# 1_ESP32Main.net
KiCad netlist of a schematic drawn in Altium Designer
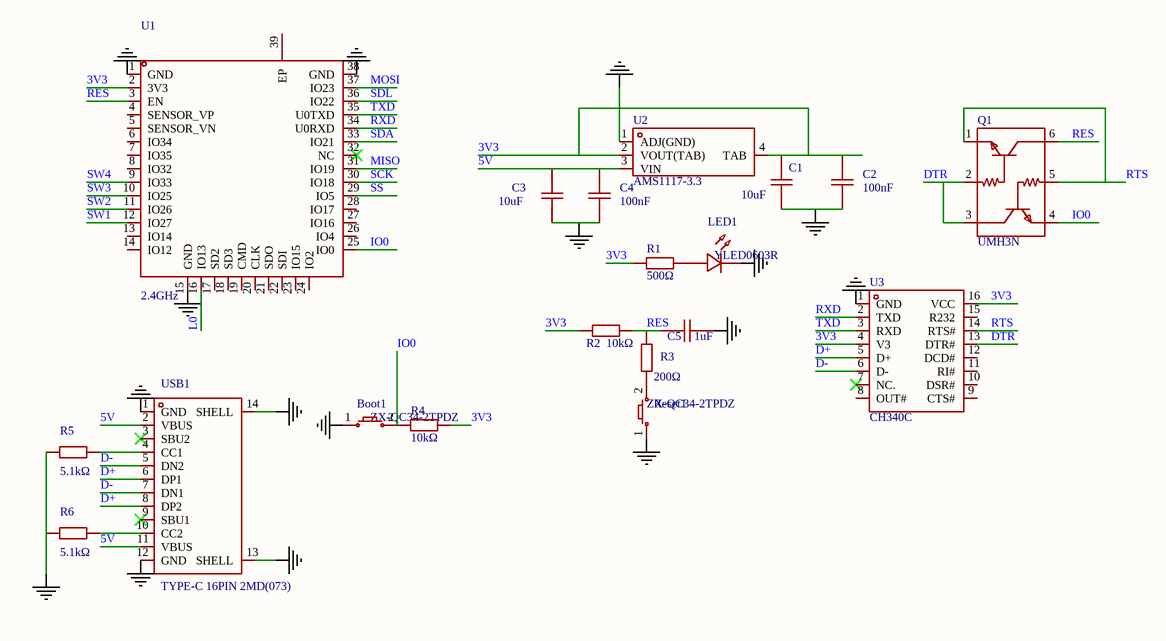
[diagram p0: 1_ESP32Main.schdoc]

(export (version "E")
  (design (tool "Eeschema 10.0.6"))
  (components
    (comp (ref "Boot1")
      (value "ZX-QC34-2TPDZ")
      (fields (field (name "MANUFACTURER") "Megastar(兆星)"))
      (libsource (lib "altium-import") (part "root_0_ZX-QC34-2TPDZ_"))
    )
    (comp (ref "C1")
      (value "10uF")
      (description "容值:10uF;精度:±20%;额定电压:25V;材质(温度系数):X5R;")
      (fields
        (field (name "MANUFACTURER") "SAMSUNG(三星)")
        (field (name "MANUFACTURER PART") "CL10A106MA8NRNC")
      )
      (libsource (lib "altium-import") (part "root_3_CL10A106MA8NRNC_"))
    )
    (comp (ref "C2")
      (value "100nF")
      (description "容值:100nF;精度:±10%;额定电压:50V;材质(温度系数):X7R;")
      (fields
        (field (name "MANUFACTURER") "HRE(芯声)")
        (field (name "MANUFACTURER PART") "CGA0603X7R104K500JT")
      )
      (libsource (lib "altium-import") (part "root_1_CGA0603X7R104K500JT_"))
    )
    (comp (ref "C3")
      (value "10uF")
      (description "容值:10uF;精度:±20%;额定电压:25V;材质(温度系数):X5R;")
      (fields
        (field (name "MANUFACTURER") "SAMSUNG(三星)")
        (field (name "MANUFACTURER PART") "CL10A106MA8NRNC")
      )
      (libsource (lib "altium-import") (part "root_1_CL10A106MA8NRNC_"))
    )
    (comp (ref "C4")
      (value "100nF")
      (description "容值:100nF;精度:±10%;额定电压:50V;材质(温度系数):X7R;")
      (fields
        (field (name "MANUFACTURER") "HRE(芯声)")
        (field (name "MANUFACTURER PART") "CGA0603X7R104K500JT")
      )
      (libsource (lib "altium-import") (part "root_1_CGA0603X7R104K500JT_"))
    )
    (comp (ref "C5")
      (value "1uF")
      (description "容值:1uF;精度:±10%;额定电压:50V;材质(温度系数):X5R;")
      (fields
        (field (name "MANUFACTURER") "SAMSUNG(三星)")
        (field (name "MANUFACTURER PART") "CL10A105KB8NNNC")
      )
      (libsource (lib "altium-import") (part "root_0_CL10A105KB8NNNC_"))
    )
    (comp (ref "LED1")
      (value "YLED0603R")
      (fields (field (name "MANUFACTURER") "YONGYUTAI(永裕泰)"))
      (libsource (lib "altium-import") (part "root_0_YLED0603R_"))
    )
    (comp (ref "Q1")
      (value "UMH3N")
      (description "晶体管类型:2个NPN-预偏置;集射极击穿电压(Vceo):50V;集电极电流(Ic):100mA;功率(Pd):150mW;")
      (fields (field (name "MANUFACTURER") "CJ(江苏长电/长晶)"))
      (libsource (lib "altium-import") (part "root_3_UMH3N_"))
    )
    (comp (ref "R1")
      (value "500Ω")
      (description "电阻类型:薄膜电阻;阻值:500Ω;精度:±0.1%;功率:100mW;温度系数:±15ppm/℃;")
      (fields (field (name "MANUFACTURER") "YAGEO(国巨)") (field (name "MANUFACTURER PART") "RT0603BRC07500RL"))
      (libsource (lib "altium-import") (part "root_0_RT0603BRC07500RL_"))
    )
    (comp (ref "R2")
      (value "10kΩ")
      (description "电阻类型:厚膜电阻;阻值:10kΩ;精度:±5%;功率:100mW;最大工作电压:75V;温度系数:±100ppm/℃;")
      (fields (field (name "MANUFACTURER") "FOJAN(富捷)") (field (name "MANUFACTURER PART") "FRC0603J103TS"))
      (libsource (lib "altium-import") (part "root_0_FRC0603J103TS_"))
    )
    (comp (ref "R3")
      (value "200Ω")
      (description "电阻类型:厚膜电阻;阻值:200Ω;精度:±1%;功率:100mW;最大工作电压:75V;温度系数:±100ppm/℃;")
      (fields
        (field (name "MANUFACTURER") "UNI-ROYAL(厚声)")
        (field (name "MANUFACTURER PART") "0603WAF2000T5E")
      )
      (libsource (lib "altium-import") (part "root_1_0603WAF2000T5E_"))
    )
    (comp (ref "R4")
      (value "10kΩ")
      (description "电阻类型:厚膜电阻;阻值:10kΩ;精度:±5%;功率:100mW;最大工作电压:75V;温度系数:±100ppm/℃;")
      (fields (field (name "MANUFACTURER") "FOJAN(富捷)") (field (name "MANUFACTURER PART") "FRC0603J103TS"))
      (libsource (lib "altium-import") (part "root_0_FRC0603J103TS_"))
    )
    (comp (ref "R5")
      (value "5.1kΩ")
      (description "电阻类型:厚膜电阻;阻值:5.1kΩ;精度:±1%;功率:100mW;最大工作电压:75V;温度系数:±100ppm/℃;")
      (fields
        (field (name "MANUFACTURER") "UNI-ROYAL(厚声)")
        (field (name "MANUFACTURER PART") "0603WAF5101T5E")
      )
      (libsource (lib "altium-import") (part "root_0_0603WAF5101T5E_"))
    )
    (comp (ref "R6")
      (value "5.1kΩ")
      (description "电阻类型:厚膜电阻;阻值:5.1kΩ;精度:±1%;功率:100mW;最大工作电压:75V;温度系数:±100ppm/℃;")
      (fields
        (field (name "MANUFACTURER") "UNI-ROYAL(厚声)")
        (field (name "MANUFACTURER PART") "0603WAF5101T5E")
      )
      (libsource (lib "altium-import") (part "root_0_0603WAF5101T5E_"))
    )
    (comp (ref "Reset1")
      (value "ZX-QC34-2TPDZ")
      (fields (field (name "MANUFACTURER") "Megastar(兆星)"))
      (libsource (lib "altium-import") (part "root_1_ZX-QC34-2TPDZ_"))
    )
    (comp (ref "U1")
      (value "2.4GHz")
      (description "核心处理器:ESP32芯片;频率:2.4GHz;天线形式:IPEX接口;发射功率:17dBm;接收灵敏度:-90dBm;")
      (fields (field (name "MANUFACTURER") "Ai-Thinker(安信可)") (field (name "MANUFACTURER PART") "ESP32-S"))
      (libsource (lib "altium-import") (part "root_0_ESP32-S_"))
    )
    (comp (ref "U2")
      (value "AMS1117-3.3")
      (description "输出类型:固定;最大输入电压:12V;输出电压:3.3V;最大输出电流:1A;电源纹波抑制比(PSRR):60dB@(120Hz);输出极性:正极;")
      (fields (field (name "MANUFACTURER") "UMW(友台半导体)"))
      (libsource (lib "altium-import") (part "root_0_AMS1117-3.3_C347222_"))
    )
    (comp (ref "U3")
      (value "CH340C")
      (description "应用功能:收发器;接口协议:USB 2.0;数据速率:2Mbps;")
      (fields (field (name "MANUFACTURER") "WCH(南京沁恒)"))
      (libsource (lib "altium-import") (part "root_0_CH340C_"))
    )
    (comp (ref "USB1")
      (value "TYPE-C 16PIN 2MD(073)")
      (description "连接器类型:Type-C;标准:USB 3.1;公母:母;安装方式:卧贴;触点数量:16P;端口数量:1;额定电流 - 电源:5A;工作温度范围:-25℃~+85℃;")
      (fields (field (name "MANUFACTURER") "SHOU HAN(首韩)"))
      (libsource (lib "altium-import") (part "root_0_TYPE-C 16PIN 2MD(073)_"))
    )
  )
  (nets
    (net (code "1") (name "/3V3") (class "Default")
      (node (ref "C1") (pin "1") (pinfunction "1_1") (pintype "passive"))
      (node (ref "C2") (pin "2") (pinfunction "2_2") (pintype "passive"))
      (node (ref "R1") (pin "1") (pinfunction "1_1") (pintype "passive"))
      (node (ref "R2") (pin "1") (pinfunction "1_1") (pintype "passive"))
      (node (ref "R4") (pin "2") (pinfunction "2_2") (pintype "passive"))
      (node (ref "U1") (pin "2") (pinfunction "3V3_2") (pintype "passive"))
      (node (ref "U2") (pin "2") (pinfunction "VOUT(TAB)_2") (pintype "passive"))
      (node (ref "U2") (pin "4") (pinfunction "TAB_4") (pintype "passive"))
      (node (ref "U3") (pin "16") (pinfunction "VCC_16") (pintype "passive"))
      (node (ref "U3") (pin "4") (pinfunction "V3_4") (pintype "passive"))
    )
    (net (code "2") (name "/5V") (class "Default")
      (node (ref "C3") (pin "2") (pinfunction "2_2") (pintype "passive"))
      (node (ref "C4") (pin "2") (pinfunction "2_2") (pintype "passive"))
      (node (ref "U2") (pin "3") (pinfunction "VIN_3") (pintype "passive"))
      (node (ref "USB1") (pin "11") (pinfunction "VBUS_11") (pintype "passive"))
      (node (ref "USB1") (pin "2") (pinfunction "VBUS_2") (pintype "passive"))
    )
    (net (code "3") (name "/D+") (class "Default")
      (node (ref "U3") (pin "5") (pinfunction "D+_5") (pintype "passive"))
      (node (ref "USB1") (pin "6") (pinfunction "DP1_6") (pintype "passive"))
      (node (ref "USB1") (pin "8") (pinfunction "DP2_8") (pintype "passive"))
    )
    (net (code "4") (name "/D-") (class "Default")
      (node (ref "U3") (pin "6") (pinfunction "D-_6") (pintype "passive"))
      (node (ref "USB1") (pin "5") (pinfunction "DN2_5") (pintype "passive"))
      (node (ref "USB1") (pin "7") (pinfunction "DN1_7") (pintype "passive"))
    )
    (net (code "5") (name "/DTR") (class "Default")
      (node (ref "Q1") (pin "2") (pinfunction "B_2") (pintype "passive"))
      (node (ref "Q1") (pin "3") (pinfunction "C_3") (pintype "passive"))
      (node (ref "U3") (pin "13") (pinfunction "DTR#_13") (pintype "passive"))
    )
    (net (code "6") (name "/IO0") (class "Default")
      (node (ref "Boot1") (pin "2") (pinfunction "2_2") (pintype "passive"))
      (node (ref "Q1") (pin "4") (pinfunction "E_4") (pintype "passive"))
      (node (ref "R4") (pin "1") (pinfunction "1_1") (pintype "passive"))
      (node (ref "U1") (pin "25") (pinfunction "IO0_25") (pintype "passive"))
    )
    (net (code "7") (name "/L0") (class "Default")
      (node (ref "U1") (pin "16") (pinfunction "IO13_16") (pintype "passive"))
    )
    (net (code "8") (name "/MISO") (class "Default")
      (node (ref "U1") (pin "31") (pinfunction "IO19_31") (pintype "passive"))
    )
    (net (code "9") (name "/MOSI") (class "Default")
      (node (ref "U1") (pin "37") (pinfunction "IO23_37") (pintype "passive"))
    )
    (net (code "10") (name "/RES") (class "Default")
      (node (ref "C5") (pin "1") (pinfunction "1_1") (pintype "passive"))
      (node (ref "Q1") (pin "6") (pinfunction "C_6") (pintype "passive"))
      (node (ref "R2") (pin "2") (pinfunction "2_2") (pintype "passive"))
      (node (ref "R3") (pin "2") (pinfunction "2_2") (pintype "passive"))
      (node (ref "U1") (pin "3") (pinfunction "EN_3") (pintype "passive"))
    )
    (net (code "11") (name "/RTS") (class "Default")
      (node (ref "Q1") (pin "1") (pinfunction "E_1") (pintype "passive"))
      (node (ref "Q1") (pin "5") (pinfunction "B_5") (pintype "passive"))
      (node (ref "U3") (pin "14") (pinfunction "RTS#_14") (pintype "passive"))
    )
    (net (code "12") (name "/RXD") (class "Default")
      (node (ref "U1") (pin "34") (pinfunction "U0RXD_34") (pintype "passive"))
      (node (ref "U3") (pin "2") (pinfunction "TXD_2") (pintype "passive"))
    )
    (net (code "13") (name "/SCK") (class "Default")
      (node (ref "U1") (pin "30") (pinfunction "IO18_30") (pintype "passive"))
    )
    (net (code "14") (name "/SDA") (class "Default")
      (node (ref "U1") (pin "33") (pinfunction "IO21_33") (pintype "passive"))
    )
    (net (code "15") (name "/SDL") (class "Default")
      (node (ref "U1") (pin "36") (pinfunction "IO22_36") (pintype "passive"))
    )
    (net (code "16") (name "/SS") (class "Default")
      (node (ref "U1") (pin "29") (pinfunction "IO5_29") (pintype "passive"))
    )
    (net (code "17") (name "/SW1") (class "Default")
      (node (ref "U1") (pin "12") (pinfunction "IO27_12") (pintype "passive"))
    )
    (net (code "18") (name "/SW2") (class "Default")
      (node (ref "U1") (pin "11") (pinfunction "IO26_11") (pintype "passive"))
    )
    (net (code "19") (name "/SW3") (class "Default")
      (node (ref "U1") (pin "10") (pinfunction "IO25_10") (pintype "passive"))
    )
    (net (code "20") (name "/SW4") (class "Default")
      (node (ref "U1") (pin "9") (pinfunction "IO33_9") (pintype "passive"))
    )
    (net (code "21") (name "/TXD") (class "Default")
      (node (ref "U1") (pin "35") (pinfunction "U0TXD_35") (pintype "passive"))
      (node (ref "U3") (pin "3") (pinfunction "RXD_3") (pintype "passive"))
    )
    (net (code "22") (name "GND") (class "Default")
      (node (ref "Boot1") (pin "1") (pinfunction "1_1") (pintype "passive"))
      (node (ref "C1") (pin "2") (pinfunction "2_2") (pintype "passive"))
      (node (ref "C2") (pin "1") (pinfunction "1_1") (pintype "passive"))
      (node (ref "C3") (pin "1") (pinfunction "1_1") (pintype "passive"))
      (node (ref "C4") (pin "1") (pinfunction "1_1") (pintype "passive"))
      (node (ref "C5") (pin "2") (pinfunction "2_2") (pintype "passive"))
      (node (ref "LED1") (pin "1") (pinfunction "C_1") (pintype "passive"))
      (node (ref "R5") (pin "1") (pinfunction "1_1") (pintype "passive"))
      (node (ref "R6") (pin "1") (pinfunction "1_1") (pintype "passive"))
      (node (ref "Reset1") (pin "1") (pinfunction "1_1") (pintype "passive"))
      (node (ref "U1") (pin "1") (pinfunction "GND_1") (pintype "passive"))
      (node (ref "U1") (pin "15") (pinfunction "GND_15") (pintype "passive"))
      (node (ref "U1") (pin "38") (pinfunction "GND_38") (pintype "passive"))
      (node (ref "U2") (pin "1") (pinfunction "ADJ(GND)_1") (pintype "passive"))
      (node (ref "U3") (pin "1") (pinfunction "GND_1") (pintype "passive"))
      (node (ref "USB1") (pin "1") (pinfunction "GND_1") (pintype "passive"))
      (node (ref "USB1") (pin "12") (pinfunction "GND_12") (pintype "passive"))
      (node (ref "USB1") (pin "13") (pinfunction "SHELL_13") (pintype "passive"))
      (node (ref "USB1") (pin "14") (pinfunction "SHELL_14") (pintype "passive"))
    )
    (net (code "23") (name "Net-(LED1-A)") (class "Default")
      (node (ref "LED1") (pin "2") (pinfunction "A_2") (pintype "passive"))
      (node (ref "R1") (pin "2") (pinfunction "2_2") (pintype "passive"))
    )
    (net (code "24") (name "Net-(R3-Pad1)") (class "Default")
      (node (ref "R3") (pin "1") (pinfunction "1_1") (pintype "passive"))
      (node (ref "Reset1") (pin "2") (pinfunction "2_2") (pintype "passive"))
    )
    (net (code "25") (name "Net-(USB1-CC1)") (class "Default")
      (node (ref "R5") (pin "2") (pinfunction "2_2") (pintype "passive"))
      (node (ref "USB1") (pin "4") (pinfunction "CC1_4") (pintype "passive"))
    )
    (net (code "26") (name "Net-(USB1-CC2)") (class "Default")
      (node (ref "R6") (pin "2") (pinfunction "2_2") (pintype "passive"))
      (node (ref "USB1") (pin "10") (pinfunction "CC2_10") (pintype "passive"))
    )
    (net (code "27") (name "unconnected-(U1-CLK-Pad20)") (class "Default")
      (node (ref "U1") (pin "20") (pinfunction "CLK_20") (pintype "passive"))
    )
    (net (code "28") (name "unconnected-(U1-CMD-Pad19)") (class "Default")
      (node (ref "U1") (pin "19") (pinfunction "CMD_19") (pintype "passive"))
    )
    (net (code "29") (name "unconnected-(U1-EP-Pad39)") (class "Default")
      (node (ref "U1") (pin "39") (pinfunction "EP_39") (pintype "passive"))
    )
    (net (code "30") (name "unconnected-(U1-IO2-Pad24)") (class "Default")
      (node (ref "U1") (pin "24") (pinfunction "IO2_24") (pintype "passive"))
    )
    (net (code "31") (name "unconnected-(U1-IO4-Pad26)") (class "Default")
      (node (ref "U1") (pin "26") (pinfunction "IO4_26") (pintype "passive"))
    )
    (net (code "32") (name "unconnected-(U1-IO12-Pad14)") (class "Default")
      (node (ref "U1") (pin "14") (pinfunction "IO12_14") (pintype "passive"))
    )
    (net (code "33") (name "unconnected-(U1-IO14-Pad13)") (class "Default")
      (node (ref "U1") (pin "13") (pinfunction "IO14_13") (pintype "passive"))
    )
    (net (code "34") (name "unconnected-(U1-IO15-Pad23)") (class "Default")
      (node (ref "U1") (pin "23") (pinfunction "IO15_23") (pintype "passive"))
    )
    (net (code "35") (name "unconnected-(U1-IO16-Pad27)") (class "Default")
      (node (ref "U1") (pin "27") (pinfunction "IO16_27") (pintype "passive"))
    )
    (net (code "36") (name "unconnected-(U1-IO17-Pad28)") (class "Default")
      (node (ref "U1") (pin "28") (pinfunction "IO17_28") (pintype "passive"))
    )
    (net (code "37") (name "unconnected-(U1-IO32-Pad8)") (class "Default")
      (node (ref "U1") (pin "8") (pinfunction "IO32_8") (pintype "passive"))
    )
    (net (code "38") (name "unconnected-(U1-IO34-Pad6)") (class "Default")
      (node (ref "U1") (pin "6") (pinfunction "IO34_6") (pintype "passive"))
    )
    (net (code "39") (name "unconnected-(U1-IO35-Pad7)") (class "Default")
      (node (ref "U1") (pin "7") (pinfunction "IO35_7") (pintype "passive"))
    )
    (net (code "40") (name "unconnected-(U1-NC-Pad32)") (class "Default")
      (node (ref "U1") (pin "32") (pinfunction "NC_32") (pintype "passive+no_connect"))
    )
    (net (code "41") (name "unconnected-(U1-SD2-Pad17)") (class "Default")
      (node (ref "U1") (pin "17") (pinfunction "SD2_17") (pintype "passive"))
    )
    (net (code "42") (name "unconnected-(U1-SD3-Pad18)") (class "Default")
      (node (ref "U1") (pin "18") (pinfunction "SD3_18") (pintype "passive"))
    )
    (net (code "43") (name "unconnected-(U1-SDI-Pad22)") (class "Default")
      (node (ref "U1") (pin "22") (pinfunction "SDI_22") (pintype "passive"))
    )
    (net (code "44") (name "unconnected-(U1-SDO-Pad21)") (class "Default")
      (node (ref "U1") (pin "21") (pinfunction "SDO_21") (pintype "passive"))
    )
    (net (code "45") (name "unconnected-(U1-SENSOR_VN-Pad5)") (class "Default")
      (node (ref "U1") (pin "5") (pinfunction "SENSOR_VN_5") (pintype "passive"))
    )
    (net (code "46") (name "unconnected-(U1-SENSOR_VP-Pad4)") (class "Default")
      (node (ref "U1") (pin "4") (pinfunction "SENSOR_VP_4") (pintype "passive"))
    )
    (net (code "47") (name "unconnected-(U3-CTS#-Pad9)") (class "Default")
      (node (ref "U3") (pin "9") (pinfunction "CTS#_9") (pintype "passive"))
    )
    (net (code "48") (name "unconnected-(U3-DCD#-Pad12)") (class "Default")
      (node (ref "U3") (pin "12") (pinfunction "DCD#_12") (pintype "passive"))
    )
    (net (code "49") (name "unconnected-(U3-DSR#-Pad10)") (class "Default")
      (node (ref "U3") (pin "10") (pinfunction "DSR#_10") (pintype "passive"))
    )
    (net (code "50") (name "unconnected-(U3-NC.-Pad7)") (class "Default")
      (node (ref "U3") (pin "7") (pinfunction "NC._7") (pintype "passive+no_connect"))
    )
    (net (code "51") (name "unconnected-(U3-OUT#-Pad8)") (class "Default")
      (node (ref "U3") (pin "8") (pinfunction "OUT#_8") (pintype "passive"))
    )
    (net (code "52") (name "unconnected-(U3-R232-Pad15)") (class "Default")
      (node (ref "U3") (pin "15") (pinfunction "R232_15") (pintype "passive"))
    )
    (net (code "53") (name "unconnected-(U3-RI#-Pad11)") (class "Default")
      (node (ref "U3") (pin "11") (pinfunction "RI#_11") (pintype "passive"))
    )
    (net (code "54") (name "unconnected-(USB1-SBU1-Pad9)") (class "Default")
      (node (ref "USB1") (pin "9") (pinfunction "SBU1_9") (pintype "passive+no_connect"))
    )
    (net (code "55") (name "unconnected-(USB1-SBU2-Pad3)") (class "Default")
      (node (ref "USB1") (pin "3") (pinfunction "SBU2_3") (pintype "passive+no_connect"))
    )
  )
)
